# Bank0-13-33.net
KiCad netlist of a schematic drawn in Altium Designer
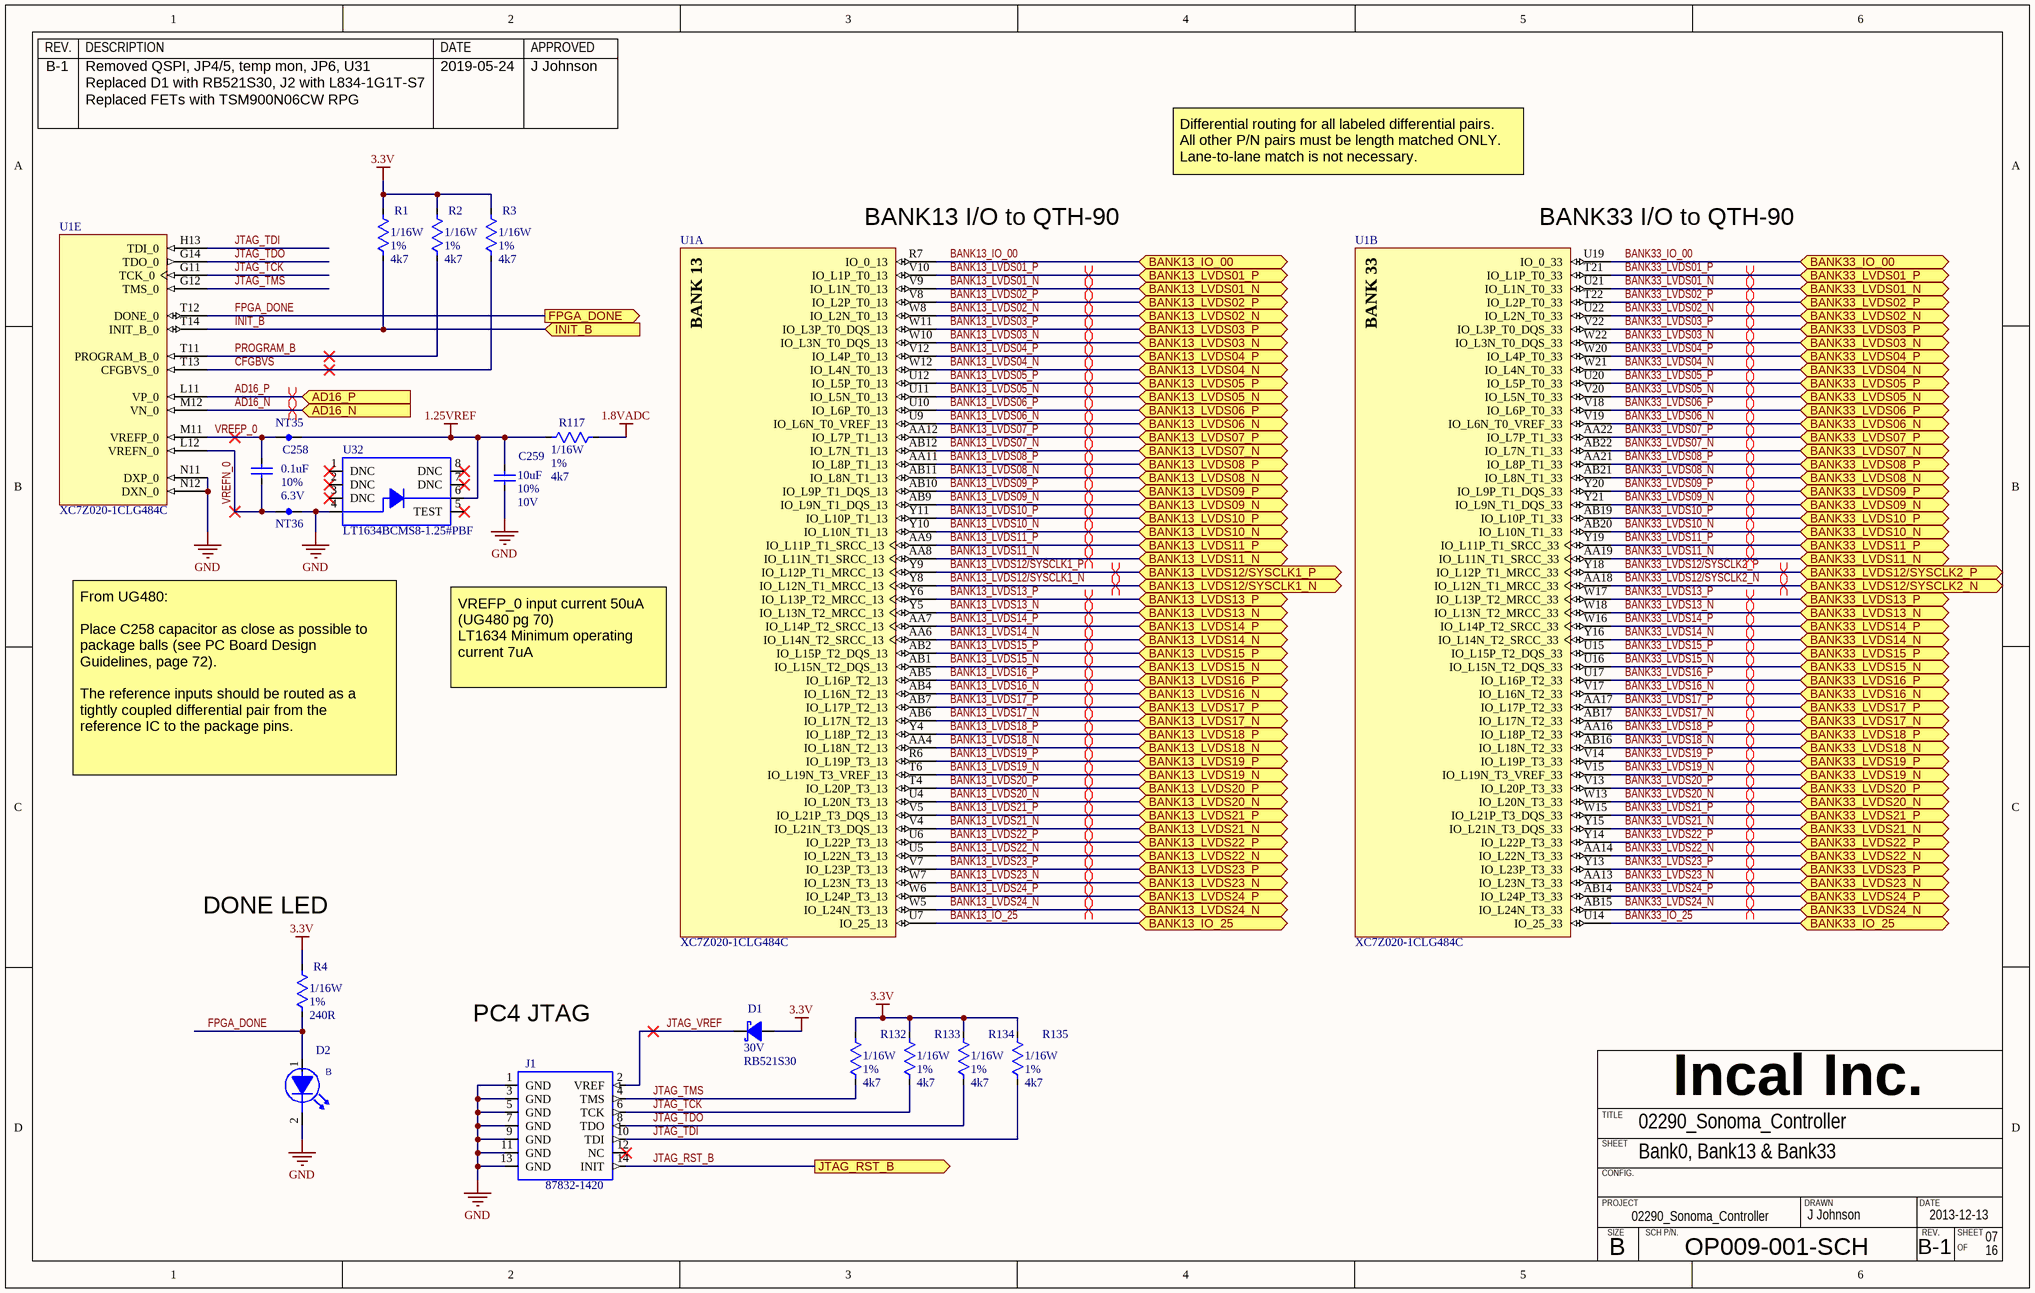
[diagram p0: Bank0-13-33.SchDoc]

(export (version "E")
  (design (tool "Eeschema 10.0.6"))
  (components
    (comp (ref "C258")
      (value "0.1uF")
      (footprint "CAPC0603X33N")
      (description "Capacitor ceramic, X5R, 0.1uF, 6.3V, 10%, -55 to +125 C, EIA0201")
      (fields
        (field (name "TOLERANCE") "10%")
        (field (name "VOLTAGE") "6.3V")
        (field (name "Comment") "CAPACITOR_NP_TYPE1")
      )
      (libsource (lib "parts") (part "CAPACITOR_NP_TYPE1"))
    )
    (comp (ref "C259")
      (value "10uF")
      (footprint "CAPC1608X38N")
      (description "Capacitor ceramic, X5R, 10uF, 10V, 10%, -55 to +85 C, EIA0603")
      (fields
        (field (name "TOLERANCE") "10%")
        (field (name "VOLTAGE") "10V")
        (field (name "Comment") "CAPACITOR_NP_TYPE1")
      )
      (libsource (lib "parts") (part "CAPACITOR_NP_TYPE1"))
    )
    (comp (ref "D1")
      (value "RB521S30")
      (footprint "SOD15080X70")
      (description "Diode schottky, 30V, 200mA, SOD-523F")
      (fields (field (name "VOLTAGE") "30V") (field (name "Comment") "DIODE_SCHOTTKY_TYPE1"))
      (libsource (lib "parts") (part "DIODE_SCHOTTKY_TYPE1"))
    )
    (comp (ref "D2")
      (value "LED_BLU")
      (footprint "LEDM1608X38N-BLU")
      (description "Led, Blue, 150mcd, SMT, LTST-C191TBKT, -20 to +80 C, 0603")
      (fields (field (name "POWER") "120mW") (field (name "VOLTAGE") "3.2V"))
      (libsource (lib "parts") (part "LED_BLU"))
    )
    (comp (ref "J1")
      (value "XILINX-JTAG-2x7")
      (footprint "87832-1420")
      (description "Connector Header 2mm, 2x7, SMT, Keyed, Shrouded, 0V, 0A, -55 to +105 C")
      (fields
        (field (name "POWER") "Pow")
        (field (name "VOLTAGE") "0V")
        (field (name "MFG PART NUMBER 1") "87832-1420")
      )
      (libsource (lib "parts") (part "XILINX-JTAG-2x7"))
    )
    (comp (ref "NT35")
      (value "NET_TIE_1X1")
      (footprint "NET_TIE_1X1")
      (description "Net Tie 1 to 1")
      (libsource (lib "parts") (part "NET_TIE_1X1"))
    )
    (comp (ref "NT36")
      (value "NET_TIE_1X1")
      (footprint "NET_TIE_1X1")
      (description "Net Tie 1 to 1")
      (libsource (lib "parts") (part "NET_TIE_1X1"))
    )
    (comp (ref "R1")
      (value "4k7")
      (footprint "RESC1005X33N")
      (description "Resistor, 4k7, 1/16W, 1%, -55 to +155 C, EIA0402")
      (fields (field (name "VOLTAGE") "50V") (field (name "POWER") "1/16W") (field (name "TOLERANCE") "1%"))
      (libsource (lib "parts") (part "RESISTOR_TYPE1"))
    )
    (comp (ref "R2")
      (value "4k7")
      (footprint "RESC1005X33N")
      (description "Resistor, 4k7, 1/16W, 1%, -55 to +155 C, EIA0402")
      (fields (field (name "VOLTAGE") "50V") (field (name "POWER") "1/16W") (field (name "TOLERANCE") "1%"))
      (libsource (lib "parts") (part "RESISTOR_TYPE1"))
    )
    (comp (ref "R3")
      (value "4k7")
      (footprint "RESC1005X33N")
      (description "Resistor, 4k7, 1/16W, 1%, -55 to +155 C, EIA0402")
      (fields (field (name "VOLTAGE") "50V") (field (name "POWER") "1/16W") (field (name "TOLERANCE") "1%"))
      (libsource (lib "parts") (part "RESISTOR_TYPE1"))
    )
    (comp (ref "R4")
      (value "240R")
      (footprint "RESC1005X33N")
      (description "Resistor, 240R, 1/16W, 1%, -50 to +155 C, EIA0402, EIA(M)1005")
      (fields (field (name "VOLTAGE") "50V") (field (name "POWER") "1/16W") (field (name "TOLERANCE") "1%"))
      (libsource (lib "parts") (part "RESISTOR_TYPE1"))
    )
    (comp (ref "R117")
      (value "4k7")
      (footprint "RESC1005X33N")
      (description "Resistor, 4k7, 1/16W, 1%, -55 to +155 C, EIA0402")
      (fields (field (name "VOLTAGE") "50V") (field (name "POWER") "1/16W") (field (name "TOLERANCE") "1%"))
      (libsource (lib "parts") (part "RESISTOR_TYPE1"))
    )
    (comp (ref "R132")
      (value "4k7")
      (footprint "RESC1005X33N")
      (description "Resistor, 4k7, 1/16W, 1%, -55 to +155 C, EIA0402")
      (fields (field (name "VOLTAGE") "50V") (field (name "POWER") "1/16W") (field (name "TOLERANCE") "1%"))
      (libsource (lib "parts") (part "RESISTOR_TYPE1"))
    )
    (comp (ref "R133")
      (value "4k7")
      (footprint "RESC1005X33N")
      (description "Resistor, 4k7, 1/16W, 1%, -55 to +155 C, EIA0402")
      (fields (field (name "VOLTAGE") "50V") (field (name "POWER") "1/16W") (field (name "TOLERANCE") "1%"))
      (libsource (lib "parts") (part "RESISTOR_TYPE1"))
    )
    (comp (ref "R134")
      (value "4k7")
      (footprint "RESC1005X33N")
      (description "Resistor, 4k7, 1/16W, 1%, -55 to +155 C, EIA0402")
      (fields (field (name "VOLTAGE") "50V") (field (name "POWER") "1/16W") (field (name "TOLERANCE") "1%"))
      (libsource (lib "parts") (part "RESISTOR_TYPE1"))
    )
    (comp (ref "R135")
      (value "4k7")
      (footprint "RESC1005X33N")
      (description "Resistor, 4k7, 1/16W, 1%, -55 to +155 C, EIA0402")
      (fields (field (name "VOLTAGE") "50V") (field (name "POWER") "1/16W") (field (name "TOLERANCE") "1%"))
      (libsource (lib "parts") (part "RESISTOR_TYPE1"))
    )
    (comp (ref "U1")
      (value "XC7Z020-1CLG484C")
      (footprint "CLG484")
      (description "667 MHz Zynq™-7000 AP SoC, 130 PS I/O, 200 FPGA I/O, 484-Ball BGA, Speed Grade 1, Commercial Grade")
      (fields (field (name "GENERIC PART NUMBER") "XC7Z020") (field (name "MANUFACTURER") "Xilinx"))
      (libsource (lib "parts") (part "XC7Z020-1CLG484C"))
    )
    (comp (ref "U32")
      (value "LT1634")
      (footprint "SOP65P490X110-8N")
      (description "Reference Shunt 1.25V, 10ppm, 0.05%")
      (fields
        (field (name "POWER") "Pow")
        (field (name "TOLERANCE") "±0.05%")
        (field (name "MFG PART NUMBER 1") "LT1634BCMS8-1.25#PBF")
      )
      (libsource (lib "parts") (part "LT1634"))
    )
  )
  (nets
    (net (code "1") (name "/AD16_N") (class "Default")
      (node (ref "U1") (pin "M12") (pinfunction "VN_0_M12") (pintype "input"))
    )
    (net (code "2") (name "/AD16_P") (class "Default")
      (node (ref "U1") (pin "L11") (pinfunction "VP_0_L11") (pintype "input"))
    )
    (net (code "3") (name "/BANK13_IO_00") (class "Default")
      (node (ref "U1") (pin "R7") (pinfunction "IO_0_13_R7") (pintype "bidirectional"))
    )
    (net (code "4") (name "/BANK13_IO_25") (class "Default")
      (node (ref "U1") (pin "U7") (pinfunction "IO_25_13_U7") (pintype "bidirectional"))
    )
    (net (code "5") (name "/BANK13_LVDS01_N") (class "Default")
      (node (ref "U1") (pin "V9") (pinfunction "IO_L1N_T0_13_V9") (pintype "bidirectional"))
    )
    (net (code "6") (name "/BANK13_LVDS01_P") (class "Default")
      (node (ref "U1") (pin "V10") (pinfunction "IO_L1P_T0_13_V10") (pintype "bidirectional"))
    )
    (net (code "7") (name "/BANK13_LVDS02_N") (class "Default")
      (node (ref "U1") (pin "W8") (pinfunction "IO_L2N_T0_13_W8") (pintype "bidirectional"))
    )
    (net (code "8") (name "/BANK13_LVDS02_P") (class "Default")
      (node (ref "U1") (pin "V8") (pinfunction "IO_L2P_T0_13_V8") (pintype "bidirectional"))
    )
    (net (code "9") (name "/BANK13_LVDS03_N") (class "Default")
      (node (ref "U1") (pin "W10") (pinfunction "IO_L3N_T0_DQS_13_W10") (pintype "bidirectional"))
    )
    (net (code "10") (name "/BANK13_LVDS03_P") (class "Default")
      (node (ref "U1") (pin "W11") (pinfunction "IO_L3P_T0_DQS_13_W11") (pintype "bidirectional"))
    )
    (net (code "11") (name "/BANK13_LVDS04_N") (class "Default")
      (node (ref "U1") (pin "W12") (pinfunction "IO_L4N_T0_13_W12") (pintype "bidirectional"))
    )
    (net (code "12") (name "/BANK13_LVDS04_P") (class "Default")
      (node (ref "U1") (pin "V12") (pinfunction "IO_L4P_T0_13_V12") (pintype "bidirectional"))
    )
    (net (code "13") (name "/BANK13_LVDS05_N") (class "Default")
      (node (ref "U1") (pin "U11") (pinfunction "IO_L5N_T0_13_U11") (pintype "bidirectional"))
    )
    (net (code "14") (name "/BANK13_LVDS05_P") (class "Default")
      (node (ref "U1") (pin "U12") (pinfunction "IO_L5P_T0_13_U12") (pintype "bidirectional"))
    )
    (net (code "15") (name "/BANK13_LVDS06_N") (class "Default")
      (node (ref "U1") (pin "U9") (pinfunction "IO_L6N_T0_VREF_13_U9") (pintype "bidirectional"))
    )
    (net (code "16") (name "/BANK13_LVDS06_P") (class "Default")
      (node (ref "U1") (pin "U10") (pinfunction "IO_L6P_T0_13_U10") (pintype "bidirectional"))
    )
    (net (code "17") (name "/BANK13_LVDS07_N") (class "Default")
      (node (ref "U1") (pin "AB12") (pinfunction "IO_L7N_T1_13_AB12") (pintype "bidirectional"))
    )
    (net (code "18") (name "/BANK13_LVDS07_P") (class "Default")
      (node (ref "U1") (pin "AA12") (pinfunction "IO_L7P_T1_13_AA12") (pintype "bidirectional"))
    )
    (net (code "19") (name "/BANK13_LVDS08_N") (class "Default")
      (node (ref "U1") (pin "AB11") (pinfunction "IO_L8N_T1_13_AB11") (pintype "bidirectional"))
    )
    (net (code "20") (name "/BANK13_LVDS08_P") (class "Default")
      (node (ref "U1") (pin "AA11") (pinfunction "IO_L8P_T1_13_AA11") (pintype "bidirectional"))
    )
    (net (code "21") (name "/BANK13_LVDS09_N") (class "Default")
      (node (ref "U1") (pin "AB9") (pinfunction "IO_L9N_T1_DQS_13_AB9") (pintype "bidirectional"))
    )
    (net (code "22") (name "/BANK13_LVDS09_P") (class "Default")
      (node (ref "U1") (pin "AB10") (pinfunction "IO_L9P_T1_DQS_13_AB10") (pintype "bidirectional"))
    )
    (net (code "23") (name "/BANK13_LVDS10_N") (class "Default")
      (node (ref "U1") (pin "Y10") (pinfunction "IO_L10N_T1_13_Y10") (pintype "bidirectional"))
    )
    (net (code "24") (name "/BANK13_LVDS10_P") (class "Default")
      (node (ref "U1") (pin "Y11") (pinfunction "IO_L10P_T1_13_Y11") (pintype "bidirectional"))
    )
    (net (code "25") (name "/BANK13_LVDS11_N") (class "Default")
      (node (ref "U1") (pin "AA8") (pinfunction "IO_L11N_T1_SRCC_13_AA8") (pintype "bidirectional"))
    )
    (net (code "26") (name "/BANK13_LVDS11_P") (class "Default")
      (node (ref "U1") (pin "AA9") (pinfunction "IO_L11P_T1_SRCC_13_AA9") (pintype "bidirectional"))
    )
    (net (code "27") (name "/BANK13_LVDS12{slash}SYSCLK1_N") (class "Default")
      (node (ref "U1") (pin "Y8") (pinfunction "IO_L12N_T1_MRCC_13_Y8") (pintype "bidirectional"))
    )
    (net (code "28") (name "/BANK13_LVDS12{slash}SYSCLK1_P") (class "Default")
      (node (ref "U1") (pin "Y9") (pinfunction "IO_L12P_T1_MRCC_13_Y9") (pintype "bidirectional"))
    )
    (net (code "29") (name "/BANK13_LVDS13_N") (class "Default")
      (node (ref "U1") (pin "Y5") (pinfunction "IO_L13N_T2_MRCC_13_Y5") (pintype "bidirectional"))
    )
    (net (code "30") (name "/BANK13_LVDS13_P") (class "Default")
      (node (ref "U1") (pin "Y6") (pinfunction "IO_L13P_T2_MRCC_13_Y6") (pintype "bidirectional"))
    )
    (net (code "31") (name "/BANK13_LVDS14_N") (class "Default")
      (node (ref "U1") (pin "AA6") (pinfunction "IO_L14N_T2_SRCC_13_AA6") (pintype "bidirectional"))
    )
    (net (code "32") (name "/BANK13_LVDS14_P") (class "Default")
      (node (ref "U1") (pin "AA7") (pinfunction "IO_L14P_T2_SRCC_13_AA7") (pintype "bidirectional"))
    )
    (net (code "33") (name "/BANK13_LVDS15_N") (class "Default")
      (node (ref "U1") (pin "AB1") (pinfunction "IO_L15N_T2_DQS_13_AB1") (pintype "bidirectional"))
    )
    (net (code "34") (name "/BANK13_LVDS15_P") (class "Default")
      (node (ref "U1") (pin "AB2") (pinfunction "IO_L15P_T2_DQS_13_AB2") (pintype "bidirectional"))
    )
    (net (code "35") (name "/BANK13_LVDS16_N") (class "Default")
      (node (ref "U1") (pin "AB4") (pinfunction "IO_L16N_T2_13_AB4") (pintype "bidirectional"))
    )
    (net (code "36") (name "/BANK13_LVDS16_P") (class "Default")
      (node (ref "U1") (pin "AB5") (pinfunction "IO_L16P_T2_13_AB5") (pintype "bidirectional"))
    )
    (net (code "37") (name "/BANK13_LVDS17_N") (class "Default")
      (node (ref "U1") (pin "AB6") (pinfunction "IO_L17N_T2_13_AB6") (pintype "bidirectional"))
    )
    (net (code "38") (name "/BANK13_LVDS17_P") (class "Default")
      (node (ref "U1") (pin "AB7") (pinfunction "IO_L17P_T2_13_AB7") (pintype "bidirectional"))
    )
    (net (code "39") (name "/BANK13_LVDS18_N") (class "Default")
      (node (ref "U1") (pin "AA4") (pinfunction "IO_L18N_T2_13_AA4") (pintype "bidirectional"))
    )
    (net (code "40") (name "/BANK13_LVDS18_P") (class "Default")
      (node (ref "U1") (pin "Y4") (pinfunction "IO_L18P_T2_13_Y4") (pintype "bidirectional"))
    )
    (net (code "41") (name "/BANK13_LVDS19_N") (class "Default")
      (node (ref "U1") (pin "T6") (pinfunction "IO_L19N_T3_VREF_13_T6") (pintype "bidirectional"))
    )
    (net (code "42") (name "/BANK13_LVDS19_P") (class "Default")
      (node (ref "U1") (pin "R6") (pinfunction "IO_L19P_T3_13_R6") (pintype "bidirectional"))
    )
    (net (code "43") (name "/BANK13_LVDS20_N") (class "Default")
      (node (ref "U1") (pin "U4") (pinfunction "IO_L20N_T3_13_U4") (pintype "bidirectional"))
    )
    (net (code "44") (name "/BANK13_LVDS20_P") (class "Default")
      (node (ref "U1") (pin "T4") (pinfunction "IO_L20P_T3_13_T4") (pintype "bidirectional"))
    )
    (net (code "45") (name "/BANK13_LVDS21_N") (class "Default")
      (node (ref "U1") (pin "V4") (pinfunction "IO_L21N_T3_DQS_13_V4") (pintype "bidirectional"))
    )
    (net (code "46") (name "/BANK13_LVDS21_P") (class "Default")
      (node (ref "U1") (pin "V5") (pinfunction "IO_L21P_T3_DQS_13_V5") (pintype "bidirectional"))
    )
    (net (code "47") (name "/BANK13_LVDS22_N") (class "Default")
      (node (ref "U1") (pin "U5") (pinfunction "IO_L22N_T3_13_U5") (pintype "bidirectional"))
    )
    (net (code "48") (name "/BANK13_LVDS22_P") (class "Default")
      (node (ref "U1") (pin "U6") (pinfunction "IO_L22P_T3_13_U6") (pintype "bidirectional"))
    )
    (net (code "49") (name "/BANK13_LVDS23_N") (class "Default")
      (node (ref "U1") (pin "W7") (pinfunction "IO_L23N_T3_13_W7") (pintype "bidirectional"))
    )
    (net (code "50") (name "/BANK13_LVDS23_P") (class "Default")
      (node (ref "U1") (pin "V7") (pinfunction "IO_L23P_T3_13_V7") (pintype "bidirectional"))
    )
    (net (code "51") (name "/BANK13_LVDS24_N") (class "Default")
      (node (ref "U1") (pin "W5") (pinfunction "IO_L24N_T3_13_W5") (pintype "bidirectional"))
    )
    (net (code "52") (name "/BANK13_LVDS24_P") (class "Default")
      (node (ref "U1") (pin "W6") (pinfunction "IO_L24P_T3_13_W6") (pintype "bidirectional"))
    )
    (net (code "53") (name "/BANK33_IO_00") (class "Default")
      (node (ref "U1") (pin "U19") (pinfunction "IO_0_33_U19") (pintype "bidirectional"))
    )
    (net (code "54") (name "/BANK33_IO_25") (class "Default")
      (node (ref "U1") (pin "U14") (pinfunction "IO_25_33_U14") (pintype "bidirectional"))
    )
    (net (code "55") (name "/BANK33_LVDS01_N") (class "Default")
      (node (ref "U1") (pin "U21") (pinfunction "IO_L1N_T0_33_U21") (pintype "bidirectional"))
    )
    (net (code "56") (name "/BANK33_LVDS01_P") (class "Default")
      (node (ref "U1") (pin "T21") (pinfunction "IO_L1P_T0_33_T21") (pintype "bidirectional"))
    )
    (net (code "57") (name "/BANK33_LVDS02_N") (class "Default")
      (node (ref "U1") (pin "U22") (pinfunction "IO_L2N_T0_33_U22") (pintype "bidirectional"))
    )
    (net (code "58") (name "/BANK33_LVDS02_P") (class "Default")
      (node (ref "U1") (pin "T22") (pinfunction "IO_L2P_T0_33_T22") (pintype "bidirectional"))
    )
    (net (code "59") (name "/BANK33_LVDS03_N") (class "Default")
      (node (ref "U1") (pin "W22") (pinfunction "IO_L3N_T0_DQS_33_W22") (pintype "bidirectional"))
    )
    (net (code "60") (name "/BANK33_LVDS03_P") (class "Default")
      (node (ref "U1") (pin "V22") (pinfunction "IO_L3P_T0_DQS_33_V22") (pintype "bidirectional"))
    )
    (net (code "61") (name "/BANK33_LVDS04_N") (class "Default")
      (node (ref "U1") (pin "W21") (pinfunction "IO_L4N_T0_33_W21") (pintype "bidirectional"))
    )
    (net (code "62") (name "/BANK33_LVDS04_P") (class "Default")
      (node (ref "U1") (pin "W20") (pinfunction "IO_L4P_T0_33_W20") (pintype "bidirectional"))
    )
    (net (code "63") (name "/BANK33_LVDS05_N") (class "Default")
      (node (ref "U1") (pin "V20") (pinfunction "IO_L5N_T0_33_V20") (pintype "bidirectional"))
    )
    (net (code "64") (name "/BANK33_LVDS05_P") (class "Default")
      (node (ref "U1") (pin "U20") (pinfunction "IO_L5P_T0_33_U20") (pintype "bidirectional"))
    )
    (net (code "65") (name "/BANK33_LVDS06_N") (class "Default")
      (node (ref "U1") (pin "V19") (pinfunction "IO_L6N_T0_VREF_33_V19") (pintype "bidirectional"))
    )
    (net (code "66") (name "/BANK33_LVDS06_P") (class "Default")
      (node (ref "U1") (pin "V18") (pinfunction "IO_L6P_T0_33_V18") (pintype "bidirectional"))
    )
    (net (code "67") (name "/BANK33_LVDS07_N") (class "Default")
      (node (ref "U1") (pin "AB22") (pinfunction "IO_L7N_T1_33_AB22") (pintype "bidirectional"))
    )
    (net (code "68") (name "/BANK33_LVDS07_P") (class "Default")
      (node (ref "U1") (pin "AA22") (pinfunction "IO_L7P_T1_33_AA22") (pintype "bidirectional"))
    )
    (net (code "69") (name "/BANK33_LVDS08_N") (class "Default")
      (node (ref "U1") (pin "AB21") (pinfunction "IO_L8N_T1_33_AB21") (pintype "bidirectional"))
    )
    (net (code "70") (name "/BANK33_LVDS08_P") (class "Default")
      (node (ref "U1") (pin "AA21") (pinfunction "IO_L8P_T1_33_AA21") (pintype "bidirectional"))
    )
    (net (code "71") (name "/BANK33_LVDS09_N") (class "Default")
      (node (ref "U1") (pin "Y21") (pinfunction "IO_L9N_T1_DQS_33_Y21") (pintype "bidirectional"))
    )
    (net (code "72") (name "/BANK33_LVDS09_P") (class "Default")
      (node (ref "U1") (pin "Y20") (pinfunction "IO_L9P_T1_DQS_33_Y20") (pintype "bidirectional"))
    )
    (net (code "73") (name "/BANK33_LVDS10_N") (class "Default")
      (node (ref "U1") (pin "AB20") (pinfunction "IO_L10N_T1_33_AB20") (pintype "bidirectional"))
    )
    (net (code "74") (name "/BANK33_LVDS10_P") (class "Default")
      (node (ref "U1") (pin "AB19") (pinfunction "IO_L10P_T1_33_AB19") (pintype "bidirectional"))
    )
    (net (code "75") (name "/BANK33_LVDS11_N") (class "Default")
      (node (ref "U1") (pin "AA19") (pinfunction "IO_L11N_T1_SRCC_33_AA19") (pintype "bidirectional"))
    )
    (net (code "76") (name "/BANK33_LVDS11_P") (class "Default")
      (node (ref "U1") (pin "Y19") (pinfunction "IO_L11P_T1_SRCC_33_Y19") (pintype "bidirectional"))
    )
    (net (code "77") (name "/BANK33_LVDS12{slash}SYSCLK2_N") (class "Default")
      (node (ref "U1") (pin "AA18") (pinfunction "IO_L12N_T1_MRCC_33_AA18") (pintype "bidirectional"))
    )
    (net (code "78") (name "/BANK33_LVDS12{slash}SYSCLK2_P") (class "Default")
      (node (ref "U1") (pin "Y18") (pinfunction "IO_L12P_T1_MRCC_33_Y18") (pintype "bidirectional"))
    )
    (net (code "79") (name "/BANK33_LVDS13_N") (class "Default")
      (node (ref "U1") (pin "W18") (pinfunction "IO_L13N_T2_MRCC_33_W18") (pintype "bidirectional"))
    )
    (net (code "80") (name "/BANK33_LVDS13_P") (class "Default")
      (node (ref "U1") (pin "W17") (pinfunction "IO_L13P_T2_MRCC_33_W17") (pintype "bidirectional"))
    )
    (net (code "81") (name "/BANK33_LVDS14_N") (class "Default")
      (node (ref "U1") (pin "Y16") (pinfunction "IO_L14N_T2_SRCC_33_Y16") (pintype "bidirectional"))
    )
    (net (code "82") (name "/BANK33_LVDS14_P") (class "Default")
      (node (ref "U1") (pin "W16") (pinfunction "IO_L14P_T2_SRCC_33_W16") (pintype "bidirectional"))
    )
    (net (code "83") (name "/BANK33_LVDS15_N") (class "Default")
      (node (ref "U1") (pin "U16") (pinfunction "IO_L15N_T2_DQS_33_U16") (pintype "bidirectional"))
    )
    (net (code "84") (name "/BANK33_LVDS15_P") (class "Default")
      (node (ref "U1") (pin "U15") (pinfunction "IO_L15P_T2_DQS_33_U15") (pintype "bidirectional"))
    )
    (net (code "85") (name "/BANK33_LVDS16_N") (class "Default")
      (node (ref "U1") (pin "V17") (pinfunction "IO_L16N_T2_33_V17") (pintype "bidirectional"))
    )
    (net (code "86") (name "/BANK33_LVDS16_P") (class "Default")
      (node (ref "U1") (pin "U17") (pinfunction "IO_L16P_T2_33_U17") (pintype "bidirectional"))
    )
    (net (code "87") (name "/BANK33_LVDS17_N") (class "Default")
      (node (ref "U1") (pin "AB17") (pinfunction "IO_L17N_T2_33_AB17") (pintype "bidirectional"))
    )
    (net (code "88") (name "/BANK33_LVDS17_P") (class "Default")
      (node (ref "U1") (pin "AA17") (pinfunction "IO_L17P_T2_33_AA17") (pintype "bidirectional"))
    )
    (net (code "89") (name "/BANK33_LVDS18_N") (class "Default")
      (node (ref "U1") (pin "AB16") (pinfunction "IO_L18N_T2_33_AB16") (pintype "bidirectional"))
    )
    (net (code "90") (name "/BANK33_LVDS18_P") (class "Default")
      (node (ref "U1") (pin "AA16") (pinfunction "IO_L18P_T2_33_AA16") (pintype "bidirectional"))
    )
    (net (code "91") (name "/BANK33_LVDS19_N") (class "Default")
      (node (ref "U1") (pin "V15") (pinfunction "IO_L19N_T3_VREF_33_V15") (pintype "bidirectional"))
    )
    (net (code "92") (name "/BANK33_LVDS19_P") (class "Default")
      (node (ref "U1") (pin "V14") (pinfunction "IO_L19P_T3_33_V14") (pintype "bidirectional"))
    )
    (net (code "93") (name "/BANK33_LVDS20_N") (class "Default")
      (node (ref "U1") (pin "W13") (pinfunction "IO_L20N_T3_33_W13") (pintype "bidirectional"))
    )
    (net (code "94") (name "/BANK33_LVDS20_P") (class "Default")
      (node (ref "U1") (pin "V13") (pinfunction "IO_L20P_T3_33_V13") (pintype "bidirectional"))
    )
    (net (code "95") (name "/BANK33_LVDS21_N") (class "Default")
      (node (ref "U1") (pin "Y15") (pinfunction "IO_L21N_T3_DQS_33_Y15") (pintype "bidirectional"))
    )
    (net (code "96") (name "/BANK33_LVDS21_P") (class "Default")
      (node (ref "U1") (pin "W15") (pinfunction "IO_L21P_T3_DQS_33_W15") (pintype "bidirectional"))
    )
    (net (code "97") (name "/BANK33_LVDS22_N") (class "Default")
      (node (ref "U1") (pin "AA14") (pinfunction "IO_L22N_T3_33_AA14") (pintype "bidirectional"))
    )
    (net (code "98") (name "/BANK33_LVDS22_P") (class "Default")
      (node (ref "U1") (pin "Y14") (pinfunction "IO_L22P_T3_33_Y14") (pintype "bidirectional"))
    )
    (net (code "99") (name "/BANK33_LVDS23_N") (class "Default")
      (node (ref "U1") (pin "AA13") (pinfunction "IO_L23N_T3_33_AA13") (pintype "bidirectional"))
    )
    (net (code "100") (name "/BANK33_LVDS23_P") (class "Default")
      (node (ref "U1") (pin "Y13") (pinfunction "IO_L23P_T3_33_Y13") (pintype "bidirectional"))
    )
    (net (code "101") (name "/BANK33_LVDS24_N") (class "Default")
      (node (ref "U1") (pin "AB15") (pinfunction "IO_L24N_T3_33_AB15") (pintype "bidirectional"))
    )
    (net (code "102") (name "/BANK33_LVDS24_P") (class "Default")
      (node (ref "U1") (pin "AB14") (pinfunction "IO_L24P_T3_33_AB14") (pintype "bidirectional"))
    )
    (net (code "103") (name "/CFGBVS") (class "Default")
      (node (ref "R3") (pin "1") (pinfunction "1_1") (pintype "passive"))
      (node (ref "U1") (pin "T13") (pinfunction "CFGBVS_0_T13") (pintype "input"))
    )
    (net (code "104") (name "/FPGA_DONE") (class "Default")
      (node (ref "D2") (pin "1") (pinfunction "A_1") (pintype "passive"))
      (node (ref "R4") (pin "1") (pinfunction "1_1") (pintype "passive"))
      (node (ref "U1") (pin "T12") (pinfunction "DONE_0_T12") (pintype "bidirectional"))
    )
    (net (code "105") (name "/INIT_B") (class "Default")
      (node (ref "R1") (pin "1") (pinfunction "1_1") (pintype "passive"))
      (node (ref "U1") (pin "T14") (pinfunction "INIT_B_0_T14") (pintype "bidirectional"))
    )
    (net (code "106") (name "/JTAG_RST_B") (class "Default")
      (node (ref "J1") (pin "14") (pinfunction "INIT_14") (pintype "output"))
    )
    (net (code "107") (name "/JTAG_TCK") (class "Default")
      (node (ref "J1") (pin "6") (pinfunction "TCK_6") (pintype "output"))
      (node (ref "R133") (pin "1") (pinfunction "1_1") (pintype "passive"))
      (node (ref "U1") (pin "G11") (pinfunction "TCK_0_G11") (pintype "input"))
    )
    (net (code "108") (name "/JTAG_TDI") (class "Default")
      (node (ref "J1") (pin "10") (pinfunction "TDI_10") (pintype "output"))
      (node (ref "R135") (pin "1") (pinfunction "1_1") (pintype "passive"))
      (node (ref "U1") (pin "H13") (pinfunction "TDI_0_H13") (pintype "input"))
    )
    (net (code "109") (name "/JTAG_TDO") (class "Default")
      (node (ref "J1") (pin "8") (pinfunction "TDO_8") (pintype "input"))
      (node (ref "R134") (pin "1") (pinfunction "1_1") (pintype "passive"))
      (node (ref "U1") (pin "G14") (pinfunction "TDO_0_G14") (pintype "output"))
    )
    (net (code "110") (name "/JTAG_TMS") (class "Default")
      (node (ref "J1") (pin "4") (pinfunction "TMS_4") (pintype "output"))
      (node (ref "R132") (pin "1") (pinfunction "1_1") (pintype "passive"))
      (node (ref "U1") (pin "G12") (pinfunction "TMS_0_G12") (pintype "input"))
    )
    (net (code "111") (name "/JTAG_VREF") (class "Default")
      (node (ref "D1") (pin "2") (pinfunction "K_2") (pintype "passive"))
      (node (ref "J1") (pin "2") (pinfunction "VREF_2") (pintype "input"))
    )
    (net (code "112") (name "/PROGRAM_B") (class "Default")
      (node (ref "R2") (pin "1") (pinfunction "1_1") (pintype "passive"))
      (node (ref "U1") (pin "T11") (pinfunction "PROGRAM_B_0_T11") (pintype "input"))
    )
    (net (code "113") (name "/VREFN_0") (class "Default")
      (node (ref "C258") (pin "2") (pinfunction "2_2") (pintype "passive"))
      (node (ref "NT36") (pin "1") (pinfunction "1_1") (pintype "passive"))
      (node (ref "U1") (pin "L12") (pinfunction "VREFN_0_L12") (pintype "input"))
    )
    (net (code "114") (name "/VREFP_0") (class "Default")
      (node (ref "C258") (pin "1") (pinfunction "1_1") (pintype "passive"))
      (node (ref "NT35") (pin "1") (pinfunction "1_1") (pintype "passive"))
      (node (ref "U1") (pin "M11") (pinfunction "VREFP_0_M11") (pintype "input"))
    )
    (net (code "115") (name "1.8VADC") (class "Default")
      (node (ref "R117") (pin "2") (pinfunction "2_2") (pintype "passive"))
    )
    (net (code "116") (name "1.25VREF") (class "Default")
      (node (ref "C259") (pin "1") (pinfunction "1_1") (pintype "passive"))
      (node (ref "NT35") (pin "2") (pinfunction "2_2") (pintype "passive"))
      (node (ref "R117") (pin "1") (pinfunction "1_1") (pintype "passive"))
      (node (ref "U32") (pin "6") (pinfunction "VOUT_6") (pintype "passive"))
    )
    (net (code "117") (name "3.3V") (class "Default")
      (node (ref "D1") (pin "1") (pinfunction "A_1") (pintype "passive"))
      (node (ref "R1") (pin "2") (pinfunction "2_2") (pintype "passive"))
      (node (ref "R132") (pin "2") (pinfunction "2_2") (pintype "passive"))
      (node (ref "R133") (pin "2") (pinfunction "2_2") (pintype "passive"))
      (node (ref "R134") (pin "2") (pinfunction "2_2") (pintype "passive"))
      (node (ref "R135") (pin "2") (pinfunction "2_2") (pintype "passive"))
      (node (ref "R2") (pin "2") (pinfunction "2_2") (pintype "passive"))
      (node (ref "R3") (pin "2") (pinfunction "2_2") (pintype "passive"))
      (node (ref "R4") (pin "2") (pinfunction "2_2") (pintype "passive"))
    )
    (net (code "118") (name "GND") (class "Default")
      (node (ref "C259") (pin "2") (pinfunction "2_2") (pintype "passive"))
      (node (ref "D2") (pin "2") (pinfunction "K_2") (pintype "passive"))
      (node (ref "J1") (pin "1") (pinfunction "GND_1") (pintype "passive"))
      (node (ref "J1") (pin "11") (pinfunction "GND_11") (pintype "passive"))
      (node (ref "J1") (pin "13") (pinfunction "GND_13") (pintype "passive"))
      (node (ref "J1") (pin "3") (pinfunction "GND_3") (pintype "passive"))
      (node (ref "J1") (pin "5") (pinfunction "GND_5") (pintype "passive"))
      (node (ref "J1") (pin "7") (pinfunction "GND_7") (pintype "passive"))
      (node (ref "J1") (pin "9") (pinfunction "GND_9") (pintype "passive"))
      (node (ref "NT36") (pin "2") (pinfunction "2_2") (pintype "passive"))
      (node (ref "U1") (pin "N11") (pinfunction "DXP_0_N11") (pintype "input"))
      (node (ref "U1") (pin "N12") (pinfunction "DXN_0_N12") (pintype "input"))
      (node (ref "U32") (pin "4") (pinfunction "GND_4") (pintype "passive"))
    )
    (net (code "119") (name "unconnected-(J1-NC-Pad12)") (class "Default")
      (node (ref "J1") (pin "12") (pinfunction "NC_12") (pintype "passive+no_connect"))
    )
    (net (code "120") (name "unconnected-(U32-DNC-Pad1)") (class "Default")
      (node (ref "U32") (pin "1") (pinfunction "DNC_1") (pintype "passive+no_connect"))
    )
    (net (code "121") (name "unconnected-(U32-DNC-Pad2)") (class "Default")
      (node (ref "U32") (pin "2") (pinfunction "DNC_2") (pintype "passive+no_connect"))
    )
    (net (code "122") (name "unconnected-(U32-DNC-Pad3)") (class "Default")
      (node (ref "U32") (pin "3") (pinfunction "DNC_3") (pintype "passive+no_connect"))
    )
    (net (code "123") (name "unconnected-(U32-DNC-Pad7)") (class "Default")
      (node (ref "U32") (pin "7") (pinfunction "DNC_7") (pintype "passive+no_connect"))
    )
    (net (code "124") (name "unconnected-(U32-DNC-Pad8)") (class "Default")
      (node (ref "U32") (pin "8") (pinfunction "DNC_8") (pintype "passive+no_connect"))
    )
    (net (code "125") (name "unconnected-(U32-TEST-Pad5)") (class "Default")
      (node (ref "U32") (pin "5") (pinfunction "TEST_5") (pintype "passive+no_connect"))
    )
  )
)
